# SCH.net
KiCad netlist of a schematic drawn in EasyEDA
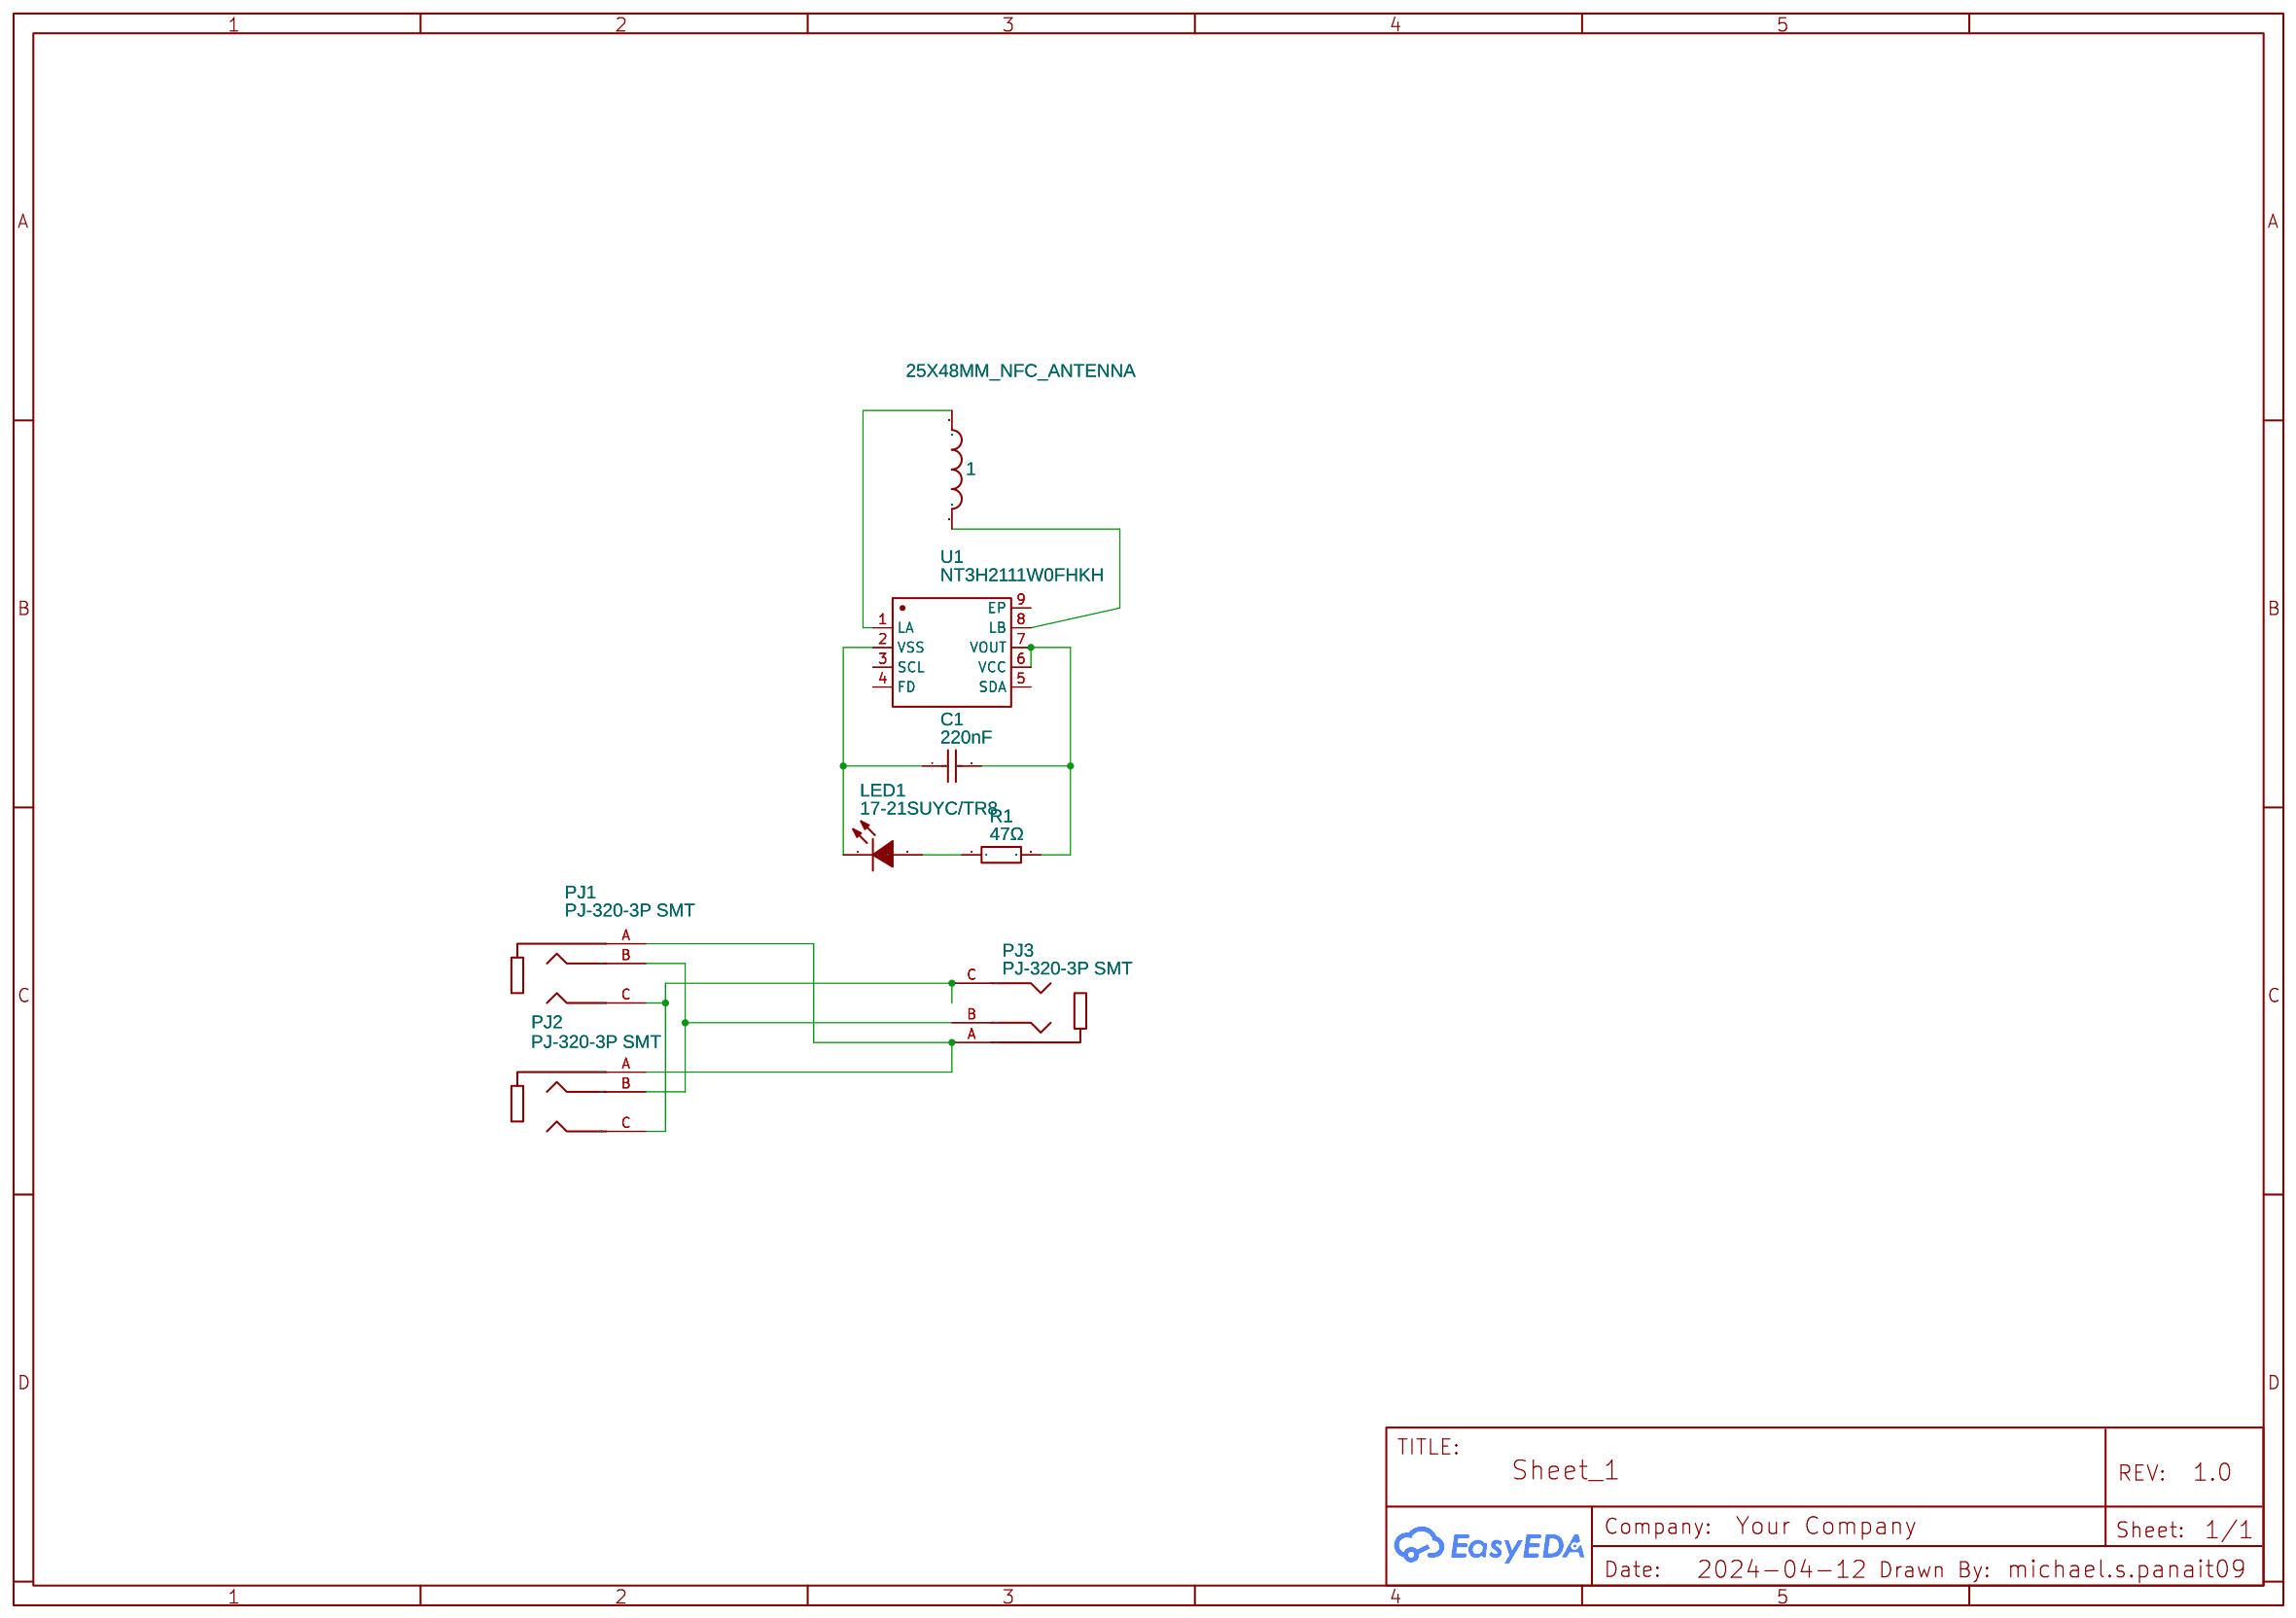
[diagram p0: schematic sheet]

(export (version "E")
  (design (tool "Eeschema 10.0.6"))
  (components
    (comp (ref "1") (value "25X48MM_NFC_ANTENNA") (libsource (lib "") (part "25X48MM_NFC_ANTENNA")))
    (comp (ref "C1")
      (value "220nF")
      (fields
        (field (name "Manufacturer Part") "CL10B224KA8NNNC")
        (field (name "Manufacturer") "SAMSUNG(三星)")
      )
      (libsource (lib "") (part "CL10B224KA8NNNC"))
    )
    (comp (ref "LED1")
      (value "17-21SUYC/TR8")
      (fields (field (name "Manufacturer Part") "KT-0805黄灯") (field (name "Manufacturer") "KENTO"))
      (libsource (lib "") (part "17-21SUYC/TR8"))
    )
    (comp (ref "PJ1")
      (value "PJ-320-3P SMT")
      (fields (field (name "Manufacturer") "SHOU HAN(首韩)"))
      (libsource (lib "") (part "PJ-320-3P SMT_1"))
    )
    (comp (ref "PJ2")
      (value "PJ-320-3P SMT")
      (fields (field (name "Manufacturer") "SHOU HAN(首韩)"))
      (libsource (lib "") (part "PJ-320-3P SMT_1"))
    )
    (comp (ref "PJ3")
      (value "PJ-320-3P SMT")
      (fields (field (name "Manufacturer") "SHOU HAN(首韩)"))
      (libsource (lib "") (part "PJ-320-3P SMT"))
    )
    (comp (ref "R1")
      (value "47Ω")
      (fields
        (field (name "Manufacturer Part") "0603WAF470JT5E")
        (field (name "Manufacturer") "UNI-ROYAL(厚声)")
      )
      (libsource (lib "") (part "0603WAF470JT5E"))
    )
    (comp (ref "U1")
      (value "NT3H2111W0FHKH")
      (fields (field (name "Manufacturer") "NXP(恩智浦)"))
      (libsource (lib "") (part "NT3H2111W0FHKH"))
    )
  )
  (nets
    (net (code "1") (name "Net-(LED1-+)") (class "Default")
      (node (ref "LED1") (pin "1") (pinfunction "+_1") (pintype "unspecified"))
      (node (ref "R1") (pin "1") (pinfunction "1_1") (pintype "input"))
    )
    (net (code "2") (name "Net-(LED1--)") (class "Default")
      (node (ref "C1") (pin "1") (pinfunction "1_1") (pintype "input"))
      (node (ref "LED1") (pin "2") (pinfunction "-_2") (pintype "unspecified"))
      (node (ref "U1") (pin "2") (pinfunction "VSS_2") (pintype "unspecified"))
    )
    (net (code "3") (name "Net-(PJ1-PadA)") (class "Default")
      (node (ref "PJ1") (pin "A") (pinfunction "A_A") (pintype "unspecified"))
      (node (ref "PJ2") (pin "A") (pinfunction "A_A") (pintype "unspecified"))
      (node (ref "PJ3") (pin "A") (pinfunction "A_A") (pintype "unspecified"))
    )
    (net (code "4") (name "Net-(PJ1-PadB)") (class "Default")
      (node (ref "PJ1") (pin "B") (pinfunction "B_B") (pintype "unspecified"))
      (node (ref "PJ2") (pin "B") (pinfunction "B_B") (pintype "unspecified"))
      (node (ref "PJ3") (pin "B") (pinfunction "B_B") (pintype "unspecified"))
    )
    (net (code "5") (name "Net-(PJ1-PadC)") (class "Default")
      (node (ref "PJ1") (pin "C") (pinfunction "C_C") (pintype "unspecified"))
      (node (ref "PJ2") (pin "C") (pinfunction "C_C") (pintype "unspecified"))
      (node (ref "PJ3") (pin "C") (pinfunction "C_C") (pintype "unspecified"))
    )
    (net (code "6") (name "Net-(U1-LA)") (class "Default")
      (node (ref "1") (pin "P$1") (pinfunction "P$1_P$1") (pintype "bidirectional"))
      (node (ref "U1") (pin "1") (pinfunction "LA_1") (pintype "unspecified"))
    )
    (net (code "7") (name "Net-(U1-LB)") (class "Default")
      (node (ref "1") (pin "P$2") (pinfunction "P$2_P$2") (pintype "bidirectional"))
      (node (ref "U1") (pin "8") (pinfunction "LB_8") (pintype "unspecified"))
    )
    (net (code "8") (name "Net-(U1-VCC)") (class "Default")
      (node (ref "C1") (pin "2") (pinfunction "2_2") (pintype "input"))
      (node (ref "R1") (pin "2") (pinfunction "2_2") (pintype "input"))
      (node (ref "U1") (pin "6") (pinfunction "VCC_6") (pintype "unspecified"))
      (node (ref "U1") (pin "7") (pinfunction "VOUT_7") (pintype "unspecified"))
    )
    (net (code "9") (name "unconnected-(U1-EP-Pad9)") (class "Default")
      (node (ref "U1") (pin "9") (pinfunction "EP_9") (pintype "unspecified"))
    )
    (net (code "10") (name "unconnected-(U1-FD-Pad4)") (class "Default")
      (node (ref "U1") (pin "4") (pinfunction "FD_4") (pintype "unspecified"))
    )
    (net (code "11") (name "unconnected-(U1-SCL-Pad3)") (class "Default")
      (node (ref "U1") (pin "3") (pinfunction "SCL_3") (pintype "unspecified"))
    )
    (net (code "12") (name "unconnected-(U1-SDA-Pad5)") (class "Default")
      (node (ref "U1") (pin "5") (pinfunction "SDA_5") (pintype "unspecified"))
    )
  )
)
